# pmc3.net
KiCad netlist of a schematic drawn in EAGLE
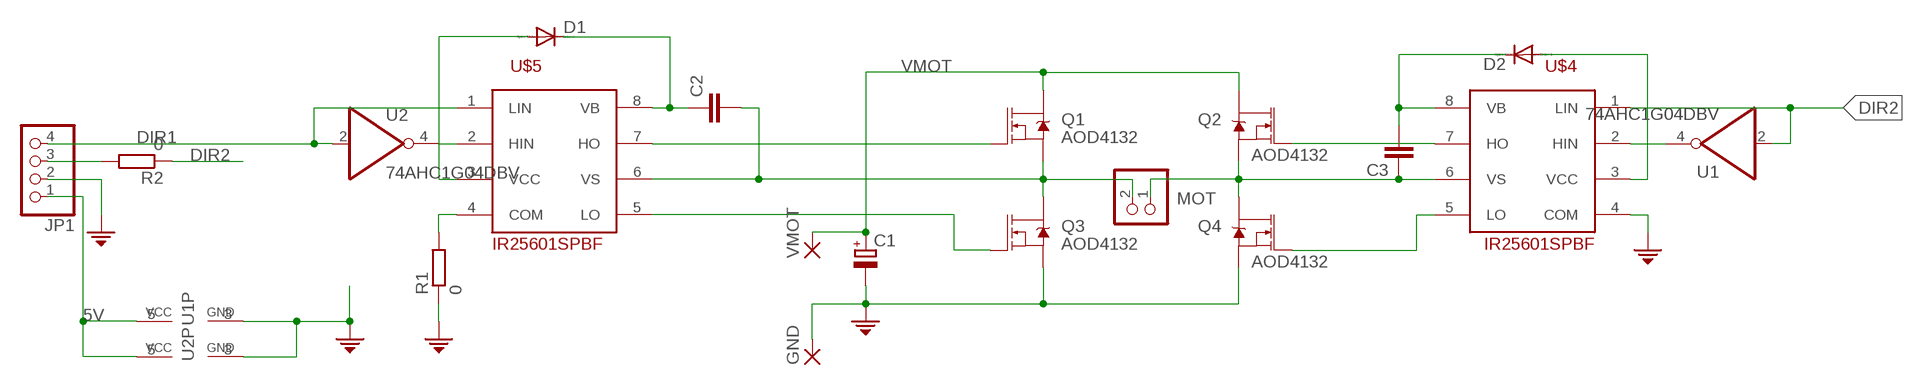
[diagram p0: schematic, sheet 1]

(export (version "E")
  (design (tool "Eeschema 10.0.6"))
  (components
    (comp (ref "C1")
      (value "CPOL-EUE5-13")
      (footprint "eagle-import:E5-13")
      (libsource (lib "eagle-import") (part "CPOL-EUE5-13"))
    )
    (comp (ref "C2")
      (value "C-EUC0805")
      (footprint "eagle-import:C0805")
      (libsource (lib "eagle-import") (part "C-EUC0805"))
    )
    (comp (ref "C3")
      (value "C-EUC0805")
      (footprint "eagle-import:C0805")
      (libsource (lib "eagle-import") (part "C-EUC0805"))
    )
    (comp (ref "D1")
      (value "DIODE-SOD123")
      (footprint "eagle-import:SOD123")
      (libsource (lib "eagle-import") (part "DIODE-SOD123"))
    )
    (comp (ref "D2")
      (value "DIODE-SOD123")
      (footprint "eagle-import:SOD123")
      (libsource (lib "eagle-import") (part "DIODE-SOD123"))
    )
    (comp (ref "GND")
      (value "SMD5")
      (footprint "eagle-import:SMD2,54-5,08")
      (libsource (lib "eagle-import") (part "SMD5"))
    )
    (comp (ref "JP1")
      (value "PINHD-1X4/90")
      (footprint "eagle-import:1X04_90")
      (libsource (lib "eagle-import") (part "PINHD-1X4/90"))
    )
    (comp (ref "MOT")
      (value "PINHD-1X2")
      (footprint "eagle-import:1X02")
      (libsource (lib "eagle-import") (part "PINHD-1X2"))
    )
    (comp (ref "Q1")
      (value "AOD4132")
      (footprint "eagle-import:DPAK")
      (libsource (lib "eagle-import") (part "MOSFET-NCH-FDD8780"))
    )
    (comp (ref "Q2")
      (value "AOD4132")
      (footprint "eagle-import:DPAK")
      (libsource (lib "eagle-import") (part "MOSFET-NCH-FDD8780"))
    )
    (comp (ref "Q3")
      (value "AOD4132")
      (footprint "eagle-import:DPAK")
      (libsource (lib "eagle-import") (part "MOSFET-NCH-FDD8780"))
    )
    (comp (ref "Q4")
      (value "AOD4132")
      (footprint "eagle-import:DPAK")
      (libsource (lib "eagle-import") (part "MOSFET-NCH-FDD8780"))
    )
    (comp (ref "R1")
      (value "0")
      (footprint "eagle-import:R1206")
      (libsource (lib "eagle-import") (part "R-EU_R1206"))
    )
    (comp (ref "R2")
      (value "0")
      (footprint "eagle-import:R1206")
      (libsource (lib "eagle-import") (part "R-EU_R1206"))
    )
    (comp (ref "U$4")
      (value "IR25601SPBF")
      (footprint "eagle-import:SO08")
      (libsource (lib "eagle-import") (part "IR25601SPBF"))
    )
    (comp (ref "U$5")
      (value "IR25601SPBF")
      (footprint "eagle-import:SO08")
      (libsource (lib "eagle-import") (part "IR25601SPBF"))
    )
    (comp (ref "U1")
      (value "74AHC1G04DBV")
      (footprint "eagle-import:SOT23-5")
      (libsource (lib "eagle-import") (part "741G04DBVAHC"))
    )
    (comp (ref "U2")
      (value "74AHC1G04DBV")
      (footprint "eagle-import:SOT23-5")
      (libsource (lib "eagle-import") (part "741G04DBVAHC"))
    )
    (comp (ref "VMOT")
      (value "SMD5")
      (footprint "eagle-import:SMD2,54-5,08")
      (libsource (lib "eagle-import") (part "SMD5"))
    )
  )
  (nets
    (net (code "1") (name "/5V") (class "Default")
      (node (ref "D1") (pin "A") (pinfunction "A_A") (pintype "passive"))
      (node (ref "D2") (pin "A") (pinfunction "A_A") (pintype "passive"))
      (node (ref "JP1") (pin "1") (pinfunction "1_1") (pintype "passive"))
      (node (ref "U$4") (pin "3") (pinfunction "VCC_3") (pintype "bidirectional"))
      (node (ref "U$5") (pin "3") (pinfunction "VCC_3") (pintype "bidirectional"))
      (node (ref "U1") (pin "5") (pinfunction "VCC_5") (pintype "power_in"))
      (node (ref "U2") (pin "5") (pinfunction "VCC_5") (pintype "power_in"))
    )
    (net (code "2") (name "/DIR1") (class "Default")
      (node (ref "JP1") (pin "4") (pinfunction "4_4") (pintype "passive"))
      (node (ref "U$5") (pin "1") (pinfunction "LIN_1") (pintype "bidirectional"))
      (node (ref "U2") (pin "2") (pinfunction "I_2") (pintype "input"))
    )
    (net (code "3") (name "/VMOT") (class "Default")
      (node (ref "C1") (pin "+") (pinfunction "+_+") (pintype "passive"))
      (node (ref "Q1") (pin "4") (pinfunction "D_4") (pintype "bidirectional"))
      (node (ref "Q2") (pin "4") (pinfunction "D_4") (pintype "bidirectional"))
      (node (ref "VMOT") (pin "1") (pinfunction "P_1") (pintype "passive"))
    )
    (net (code "4") (name "DIR2") (class "Default")
      (node (ref "R2") (pin "1") (pinfunction "1_1") (pintype "passive"))
      (node (ref "U$4") (pin "1") (pinfunction "LIN_1") (pintype "bidirectional"))
      (node (ref "U1") (pin "2") (pinfunction "I_2") (pintype "input"))
    )
    (net (code "5") (name "GND") (class "Default")
      (node (ref "C1") (pin "-") (pinfunction "-_-") (pintype "passive"))
      (node (ref "GND") (pin "1") (pinfunction "P_1") (pintype "passive"))
      (node (ref "JP1") (pin "2") (pinfunction "2_2") (pintype "passive"))
      (node (ref "Q3") (pin "3") (pinfunction "S_3") (pintype "bidirectional"))
      (node (ref "Q4") (pin "3") (pinfunction "S_3") (pintype "bidirectional"))
      (node (ref "R1") (pin "1") (pinfunction "1_1") (pintype "passive"))
      (node (ref "U$4") (pin "4") (pinfunction "COM_4") (pintype "bidirectional"))
      (node (ref "U1") (pin "3") (pinfunction "GND_3") (pintype "power_in"))
      (node (ref "U2") (pin "3") (pinfunction "GND_3") (pintype "power_in"))
    )
    (net (code "6") (name "Net-(JP1-Pad3)") (class "Default")
      (node (ref "JP1") (pin "3") (pinfunction "3_3") (pintype "passive"))
      (node (ref "R2") (pin "2") (pinfunction "2_2") (pintype "passive"))
    )
    (net (code "7") (name "Net-(Q1-G)") (class "Default")
      (node (ref "Q1") (pin "1") (pinfunction "G_1") (pintype "bidirectional"))
      (node (ref "U$5") (pin "7") (pinfunction "HO_7") (pintype "bidirectional"))
    )
    (net (code "8") (name "Net-(Q1-S)") (class "Default")
      (node (ref "C2") (pin "2") (pinfunction "2_2") (pintype "passive"))
      (node (ref "MOT") (pin "2") (pinfunction "2_2") (pintype "passive"))
      (node (ref "Q1") (pin "3") (pinfunction "S_3") (pintype "bidirectional"))
      (node (ref "Q3") (pin "4") (pinfunction "D_4") (pintype "bidirectional"))
      (node (ref "U$5") (pin "6") (pinfunction "VS_6") (pintype "bidirectional"))
    )
    (net (code "9") (name "Net-(Q2-G)") (class "Default")
      (node (ref "Q2") (pin "1") (pinfunction "G_1") (pintype "bidirectional"))
      (node (ref "U$4") (pin "7") (pinfunction "HO_7") (pintype "bidirectional"))
    )
    (net (code "10") (name "Net-(Q2-S)") (class "Default")
      (node (ref "C3") (pin "1") (pinfunction "1_1") (pintype "passive"))
      (node (ref "MOT") (pin "1") (pinfunction "1_1") (pintype "passive"))
      (node (ref "Q2") (pin "3") (pinfunction "S_3") (pintype "bidirectional"))
      (node (ref "Q4") (pin "4") (pinfunction "D_4") (pintype "bidirectional"))
      (node (ref "U$4") (pin "6") (pinfunction "VS_6") (pintype "bidirectional"))
    )
    (net (code "11") (name "Net-(Q3-G)") (class "Default")
      (node (ref "Q3") (pin "1") (pinfunction "G_1") (pintype "bidirectional"))
      (node (ref "U$5") (pin "5") (pinfunction "LO_5") (pintype "bidirectional"))
    )
    (net (code "12") (name "Net-(Q4-G)") (class "Default")
      (node (ref "Q4") (pin "1") (pinfunction "G_1") (pintype "bidirectional"))
      (node (ref "U$4") (pin "5") (pinfunction "LO_5") (pintype "bidirectional"))
    )
    (net (code "13") (name "Net-(U$4-HIN)") (class "Default")
      (node (ref "U$4") (pin "2") (pinfunction "HIN_2") (pintype "bidirectional"))
      (node (ref "U1") (pin "4") (pinfunction "O_4") (pintype "output"))
    )
    (net (code "14") (name "Net-(U$4-VB)") (class "Default")
      (node (ref "C3") (pin "2") (pinfunction "2_2") (pintype "passive"))
      (node (ref "D2") (pin "C") (pinfunction "C_C") (pintype "passive"))
      (node (ref "U$4") (pin "8") (pinfunction "VB_8") (pintype "bidirectional"))
    )
    (net (code "15") (name "Net-(U$5-COM)") (class "Default")
      (node (ref "R1") (pin "2") (pinfunction "2_2") (pintype "passive"))
      (node (ref "U$5") (pin "4") (pinfunction "COM_4") (pintype "bidirectional"))
    )
    (net (code "16") (name "Net-(U$5-HIN)") (class "Default")
      (node (ref "U$5") (pin "2") (pinfunction "HIN_2") (pintype "bidirectional"))
      (node (ref "U2") (pin "4") (pinfunction "O_4") (pintype "output"))
    )
    (net (code "17") (name "Net-(U$5-VB)") (class "Default")
      (node (ref "C2") (pin "1") (pinfunction "1_1") (pintype "passive"))
      (node (ref "D1") (pin "C") (pinfunction "C_C") (pintype "passive"))
      (node (ref "U$5") (pin "8") (pinfunction "VB_8") (pintype "bidirectional"))
    )
  )
)
